# radio.net
KiCad netlist of a schematic drawn in EAGLE
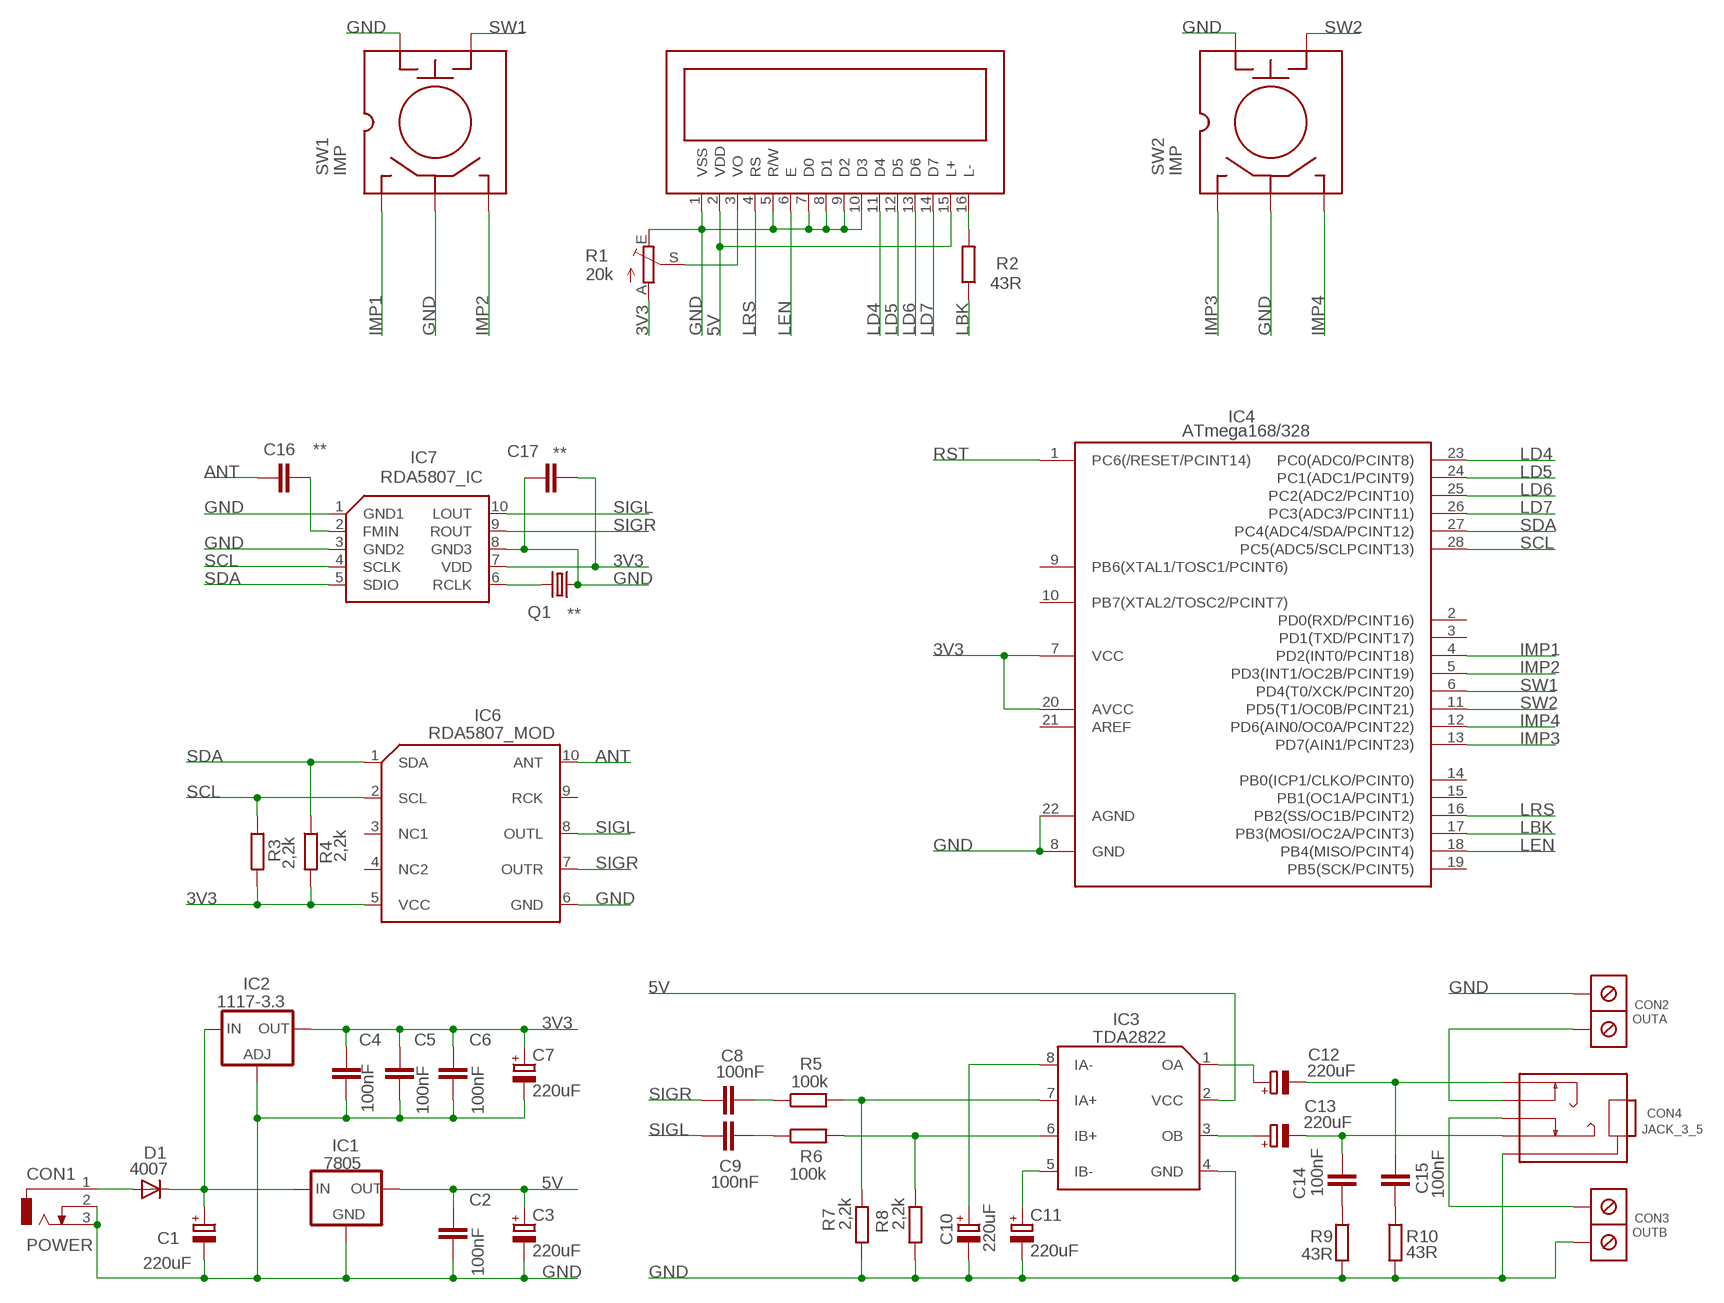
[diagram p0: schematic, sheet 1]

(export (version "E")
  (design (tool "Eeschema 10.0.6"))
  (components
    (comp (ref "C1")
      (value "220uF")
      (footprint "eagle-import:E2,5-7")
      (libsource (lib "eagle-import") (part "CPOL-EUE2.5-7"))
    )
    (comp (ref "C2")
      (value "100nF")
      (footprint "eagle-import:C050-030X075")
      (libsource (lib "eagle-import") (part "C-EU050-030X075"))
    )
    (comp (ref "C3")
      (value "220uF")
      (footprint "eagle-import:E2,5-7")
      (libsource (lib "eagle-import") (part "CPOL-EUE2.5-7"))
    )
    (comp (ref "C4")
      (value "100nF")
      (footprint "eagle-import:C050-030X075")
      (libsource (lib "eagle-import") (part "C-EU050-030X075"))
    )
    (comp (ref "C5")
      (value "100nF")
      (footprint "eagle-import:C050-030X075")
      (libsource (lib "eagle-import") (part "C-EU050-030X075"))
    )
    (comp (ref "C6")
      (value "100nF")
      (footprint "eagle-import:C050-030X075")
      (libsource (lib "eagle-import") (part "C-EU050-030X075"))
    )
    (comp (ref "C7")
      (value "220uF")
      (footprint "eagle-import:E2,5-7")
      (libsource (lib "eagle-import") (part "CPOL-EUE2.5-7"))
    )
    (comp (ref "C8")
      (value "100nF")
      (footprint "eagle-import:C050-030X075")
      (libsource (lib "eagle-import") (part "C-EU050-030X075"))
    )
    (comp (ref "C9")
      (value "100nF")
      (footprint "eagle-import:C050-030X075")
      (libsource (lib "eagle-import") (part "C-EU050-030X075"))
    )
    (comp (ref "C10")
      (value "220uF")
      (footprint "eagle-import:E2,5-7")
      (libsource (lib "eagle-import") (part "CPOL-EUE2.5-7"))
    )
    (comp (ref "C11")
      (value "220uF")
      (footprint "eagle-import:E2,5-7")
      (libsource (lib "eagle-import") (part "CPOL-EUE2.5-7"))
    )
    (comp (ref "C12")
      (value "220uF")
      (footprint "eagle-import:E2,5-7")
      (libsource (lib "eagle-import") (part "CPOL-EUE2.5-7"))
    )
    (comp (ref "C13")
      (value "220uF")
      (footprint "eagle-import:E2,5-7")
      (libsource (lib "eagle-import") (part "CPOL-EUE2.5-7"))
    )
    (comp (ref "C14")
      (value "100nF")
      (footprint "eagle-import:C050-030X075")
      (libsource (lib "eagle-import") (part "C-EU050-030X075"))
    )
    (comp (ref "C15")
      (value "100nF")
      (footprint "eagle-import:C050-030X075")
      (libsource (lib "eagle-import") (part "C-EU050-030X075"))
    )
    (comp (ref "C16")
      (value "**")
      (footprint "eagle-import:C0805K")
      (libsource (lib "eagle-import") (part "C-EUC0805K"))
    )
    (comp (ref "C17")
      (value "**")
      (footprint "eagle-import:C0805K")
      (libsource (lib "eagle-import") (part "C-EUC0805K"))
    )
    (comp (ref "CON1")
      (value "POWER")
      (footprint "eagle-import:DCJ0202")
      (libsource (lib "eagle-import") (part "DCJ0202"))
    )
    (comp (ref "CON2")
      (value "OUTA")
      (footprint "eagle-import:ARK2_300")
      (libsource (lib "eagle-import") (part "ARK2/300"))
    )
    (comp (ref "CON3")
      (value "OUTB")
      (footprint "eagle-import:ARK2_300")
      (libsource (lib "eagle-import") (part "ARK2/300"))
    )
    (comp (ref "CON4")
      (value "JACK_3_5")
      (footprint "eagle-import:JACK_3_5")
      (libsource (lib "eagle-import") (part "JACK_3_5"))
    )
    (comp (ref "D1")
      (value "4007")
      (footprint "eagle-import:DO41-10")
      (libsource (lib "eagle-import") (part "1N4004"))
    )
    (comp (ref "IC1")
      (value "7805")
      (footprint "eagle-import:78XXS")
      (libsource (lib "eagle-import") (part "78XXS"))
    )
    (comp (ref "IC2")
      (value "1117-3.3")
      (footprint "eagle-import:317TS")
      (libsource (lib "eagle-import") (part "LM317TS"))
    )
    (comp (ref "IC3")
      (value "TDA2822")
      (footprint "eagle-import:DIL8")
      (libsource (lib "eagle-import") (part "TDA2822"))
    )
    (comp (ref "IC4")
      (value "ATmega168/328")
      (footprint "eagle-import:DIL28-3")
      (libsource (lib "eagle-import") (part "MEGA48/88/168-PU"))
    )
    (comp (ref "IC5")
      (value "LCD16X2")
      (footprint "eagle-import:LCD16X2")
      (libsource (lib "eagle-import") (part "LCD16X2"))
    )
    (comp (ref "IC6")
      (value "RDA5807_MOD")
      (footprint "eagle-import:RDA5807_MOD")
      (libsource (lib "eagle-import") (part "RDA5807_MOD"))
    )
    (comp (ref "IC7")
      (value "RDA5807_IC")
      (footprint "eagle-import:MSOP10")
      (libsource (lib "eagle-import") (part "RDA5807_IC"))
    )
    (comp (ref "Q1")
      (value "**")
      (footprint "eagle-import:TC38H")
      (libsource (lib "eagle-import") (part "CRYSTALTC38H"))
    )
    (comp (ref "R1")
      (value "20k")
      (footprint "eagle-import:CA6V")
      (libsource (lib "eagle-import") (part "TRIM_EU-CA6V"))
    )
    (comp (ref "R2")
      (value "43R")
      (footprint "eagle-import:0207_7")
      (libsource (lib "eagle-import") (part "R-EU_0207/7"))
    )
    (comp (ref "R3")
      (value "2,2k")
      (footprint "eagle-import:0207_7")
      (libsource (lib "eagle-import") (part "R-EU_0207/7"))
    )
    (comp (ref "R4")
      (value "2,2k")
      (footprint "eagle-import:0207_7")
      (libsource (lib "eagle-import") (part "R-EU_0207/7"))
    )
    (comp (ref "R5")
      (value "100k")
      (footprint "eagle-import:0207_7")
      (libsource (lib "eagle-import") (part "R-EU_0207/7"))
    )
    (comp (ref "R6")
      (value "100k")
      (footprint "eagle-import:0207_7")
      (libsource (lib "eagle-import") (part "R-EU_0207/7"))
    )
    (comp (ref "R7")
      (value "2,2k")
      (footprint "eagle-import:0207_7")
      (libsource (lib "eagle-import") (part "R-EU_0207/7"))
    )
    (comp (ref "R8")
      (value "2,2k")
      (footprint "eagle-import:0207_7")
      (libsource (lib "eagle-import") (part "R-EU_0207/7"))
    )
    (comp (ref "R9")
      (value "43R")
      (footprint "eagle-import:0207_7")
      (libsource (lib "eagle-import") (part "R-EU_0207/7"))
    )
    (comp (ref "R10")
      (value "43R")
      (footprint "eagle-import:0207_7")
      (libsource (lib "eagle-import") (part "R-EU_0207/7"))
    )
    (comp (ref "SW1")
      (value "IMP")
      (footprint "eagle-import:IMP")
      (libsource (lib "eagle-import") (part "IMP"))
    )
    (comp (ref "SW2")
      (value "IMP")
      (footprint "eagle-import:IMP")
      (libsource (lib "eagle-import") (part "IMP"))
    )
  )
  (nets
    (net (code "1") (name "/3V3") (class "Default")
      (node (ref "C17") (pin "2") (pinfunction "2_2") (pintype "passive"))
      (node (ref "C4") (pin "1") (pinfunction "1_1") (pintype "passive"))
      (node (ref "C5") (pin "1") (pinfunction "1_1") (pintype "passive"))
      (node (ref "C6") (pin "1") (pinfunction "1_1") (pintype "passive"))
      (node (ref "C7") (pin "+") (pinfunction "+_+") (pintype "passive"))
      (node (ref "IC2") (pin "2") (pinfunction "OUT_2") (pintype "passive"))
      (node (ref "IC4") (pin "20") (pinfunction "AVCC_20") (pintype "passive"))
      (node (ref "IC4") (pin "7") (pinfunction "VCC_7") (pintype "power_in"))
      (node (ref "IC6") (pin "5") (pinfunction "VCC_5") (pintype "bidirectional"))
      (node (ref "IC7") (pin "7") (pinfunction "VDD_7") (pintype "bidirectional"))
      (node (ref "R1") (pin "A") (pinfunction "A_A") (pintype "passive"))
      (node (ref "R3") (pin "2") (pinfunction "2_2") (pintype "passive"))
      (node (ref "R4") (pin "2") (pinfunction "2_2") (pintype "passive"))
    )
    (net (code "2") (name "/5V") (class "Default")
      (node (ref "C2") (pin "1") (pinfunction "1_1") (pintype "passive"))
      (node (ref "C3") (pin "+") (pinfunction "+_+") (pintype "passive"))
      (node (ref "IC1") (pin "OUT") (pinfunction "OUT_OUT") (pintype "passive"))
      (node (ref "IC3") (pin "2") (pinfunction "VCC_2") (pintype "bidirectional"))
      (node (ref "IC5") (pin "15") (pinfunction "L+_15") (pintype "bidirectional"))
      (node (ref "IC5") (pin "2") (pinfunction "VDD_2") (pintype "bidirectional"))
    )
    (net (code "3") (name "/ANT") (class "Default")
      (node (ref "C16") (pin "1") (pinfunction "1_1") (pintype "passive"))
      (node (ref "IC6") (pin "10") (pinfunction "ANT_10") (pintype "bidirectional"))
    )
    (net (code "4") (name "/GND") (class "Default")
      (node (ref "C1") (pin "-") (pinfunction "-_-") (pintype "passive"))
      (node (ref "C10") (pin "-") (pinfunction "-_-") (pintype "passive"))
      (node (ref "C11") (pin "-") (pinfunction "-_-") (pintype "passive"))
      (node (ref "C17") (pin "1") (pinfunction "1_1") (pintype "passive"))
      (node (ref "C2") (pin "2") (pinfunction "2_2") (pintype "passive"))
      (node (ref "C3") (pin "-") (pinfunction "-_-") (pintype "passive"))
      (node (ref "C4") (pin "2") (pinfunction "2_2") (pintype "passive"))
      (node (ref "C5") (pin "2") (pinfunction "2_2") (pintype "passive"))
      (node (ref "C6") (pin "2") (pinfunction "2_2") (pintype "passive"))
      (node (ref "C7") (pin "-") (pinfunction "-_-") (pintype "passive"))
      (node (ref "CON1") (pin "2") (pinfunction "2_2") (pintype "passive"))
      (node (ref "CON1") (pin "3") (pinfunction "3_3") (pintype "passive"))
      (node (ref "CON2") (pin "2") (pinfunction "2_2") (pintype "bidirectional"))
      (node (ref "CON3") (pin "1") (pinfunction "1_1") (pintype "bidirectional"))
      (node (ref "CON4") (pin "G") (pinfunction "G_G") (pintype "bidirectional"))
      (node (ref "IC1") (pin "GND") (pinfunction "GND_GND") (pintype "input"))
      (node (ref "IC2") (pin "1") (pinfunction "ADJ_1") (pintype "input"))
      (node (ref "IC3") (pin "4") (pinfunction "GND_4") (pintype "bidirectional"))
      (node (ref "IC4") (pin "22") (pinfunction "AGND_22") (pintype "power_in"))
      (node (ref "IC4") (pin "8") (pinfunction "GND_8") (pintype "power_in"))
      (node (ref "IC5") (pin "1") (pinfunction "VSS_1") (pintype "bidirectional"))
      (node (ref "IC5") (pin "10") (pinfunction "D3_10") (pintype "bidirectional"))
      (node (ref "IC5") (pin "5") (pinfunction "R/W_5") (pintype "bidirectional"))
      (node (ref "IC5") (pin "7") (pinfunction "D0_7") (pintype "bidirectional"))
      (node (ref "IC5") (pin "8") (pinfunction "D1_8") (pintype "bidirectional"))
      (node (ref "IC5") (pin "9") (pinfunction "D2_9") (pintype "bidirectional"))
      (node (ref "IC6") (pin "6") (pinfunction "GND_6") (pintype "bidirectional"))
      (node (ref "IC7") (pin "1") (pinfunction "GND1_1") (pintype "bidirectional"))
      (node (ref "IC7") (pin "3") (pinfunction "GND2_3") (pintype "bidirectional"))
      (node (ref "IC7") (pin "8") (pinfunction "GND3_8") (pintype "bidirectional"))
      (node (ref "Q1") (pin "1") (pinfunction "1_1") (pintype "passive"))
      (node (ref "R1") (pin "E") (pinfunction "E_E") (pintype "passive"))
      (node (ref "R10") (pin "2") (pinfunction "2_2") (pintype "passive"))
      (node (ref "R7") (pin "2") (pinfunction "2_2") (pintype "passive"))
      (node (ref "R8") (pin "2") (pinfunction "2_2") (pintype "passive"))
      (node (ref "R9") (pin "2") (pinfunction "2_2") (pintype "passive"))
      (node (ref "SW1") (pin "2") (pinfunction "2_2") (pintype "bidirectional"))
      (node (ref "SW1") (pin "5") (pinfunction "5_5") (pintype "bidirectional"))
      (node (ref "SW2") (pin "2") (pinfunction "2_2") (pintype "bidirectional"))
      (node (ref "SW2") (pin "5") (pinfunction "5_5") (pintype "bidirectional"))
    )
    (net (code "5") (name "/IMP1") (class "Default")
      (node (ref "IC4") (pin "4") (pinfunction "PD2(INT0/PCINT18)_4") (pintype "bidirectional"))
      (node (ref "SW1") (pin "1") (pinfunction "1_1") (pintype "bidirectional"))
    )
    (net (code "6") (name "/IMP2") (class "Default")
      (node (ref "IC4") (pin "5") (pinfunction "PD3(INT1/OC2B/PCINT19)_5") (pintype "bidirectional"))
      (node (ref "SW1") (pin "3") (pinfunction "3_3") (pintype "bidirectional"))
    )
    (net (code "7") (name "/IMP3") (class "Default")
      (node (ref "IC4") (pin "13") (pinfunction "PD7(AIN1/PCINT23)_13") (pintype "bidirectional"))
      (node (ref "SW2") (pin "1") (pinfunction "1_1") (pintype "bidirectional"))
    )
    (net (code "8") (name "/IMP4") (class "Default")
      (node (ref "IC4") (pin "12") (pinfunction "PD6(AIN0/OC0A/PCINT22)_12") (pintype "bidirectional"))
      (node (ref "SW2") (pin "3") (pinfunction "3_3") (pintype "bidirectional"))
    )
    (net (code "9") (name "/LBK") (class "Default")
      (node (ref "IC4") (pin "17") (pinfunction "PB3(MOSI/OC2A/PCINT3)_17") (pintype "bidirectional"))
      (node (ref "R2") (pin "1") (pinfunction "1_1") (pintype "passive"))
    )
    (net (code "10") (name "/LD4") (class "Default")
      (node (ref "IC4") (pin "23") (pinfunction "PC0(ADC0/PCINT8)_23") (pintype "bidirectional"))
      (node (ref "IC5") (pin "11") (pinfunction "D4_11") (pintype "bidirectional"))
    )
    (net (code "11") (name "/LD5") (class "Default")
      (node (ref "IC4") (pin "24") (pinfunction "PC1(ADC1/PCINT9)_24") (pintype "bidirectional"))
      (node (ref "IC5") (pin "12") (pinfunction "D5_12") (pintype "bidirectional"))
    )
    (net (code "12") (name "/LD6") (class "Default")
      (node (ref "IC4") (pin "25") (pinfunction "PC2(ADC2/PCINT10)_25") (pintype "bidirectional"))
      (node (ref "IC5") (pin "13") (pinfunction "D6_13") (pintype "bidirectional"))
    )
    (net (code "13") (name "/LD7") (class "Default")
      (node (ref "IC4") (pin "26") (pinfunction "PC3(ADC3/PCINT11)_26") (pintype "bidirectional"))
      (node (ref "IC5") (pin "14") (pinfunction "D7_14") (pintype "bidirectional"))
    )
    (net (code "14") (name "/LEN") (class "Default")
      (node (ref "IC4") (pin "18") (pinfunction "PB4(MISO/PCINT4)_18") (pintype "bidirectional"))
      (node (ref "IC5") (pin "6") (pinfunction "E_6") (pintype "bidirectional"))
    )
    (net (code "15") (name "/LRS") (class "Default")
      (node (ref "IC4") (pin "16") (pinfunction "PB2(SS/OC1B/PCINT2)_16") (pintype "bidirectional"))
      (node (ref "IC5") (pin "4") (pinfunction "RS_4") (pintype "bidirectional"))
    )
    (net (code "16") (name "/RST") (class "Default")
      (node (ref "IC4") (pin "1") (pinfunction "PC6(/RESET/PCINT14)_1") (pintype "bidirectional"))
    )
    (net (code "17") (name "/SCL") (class "Default")
      (node (ref "IC4") (pin "28") (pinfunction "PC5(ADC5/SCLPCINT13)_28") (pintype "bidirectional"))
      (node (ref "IC6") (pin "2") (pinfunction "SCL_2") (pintype "bidirectional"))
      (node (ref "IC7") (pin "4") (pinfunction "SCLK_4") (pintype "bidirectional"))
      (node (ref "R3") (pin "1") (pinfunction "1_1") (pintype "passive"))
    )
    (net (code "18") (name "/SDA") (class "Default")
      (node (ref "IC4") (pin "27") (pinfunction "PC4(ADC4/SDA/PCINT12)_27") (pintype "bidirectional"))
      (node (ref "IC6") (pin "1") (pinfunction "SDA_1") (pintype "bidirectional"))
      (node (ref "IC7") (pin "5") (pinfunction "SDIO_5") (pintype "bidirectional"))
      (node (ref "R4") (pin "1") (pinfunction "1_1") (pintype "passive"))
    )
    (net (code "19") (name "/SIGL") (class "Default")
      (node (ref "C9") (pin "1") (pinfunction "1_1") (pintype "passive"))
      (node (ref "IC6") (pin "8") (pinfunction "OUTL_8") (pintype "bidirectional"))
      (node (ref "IC7") (pin "10") (pinfunction "LOUT_10") (pintype "bidirectional"))
    )
    (net (code "20") (name "/SIGR") (class "Default")
      (node (ref "C8") (pin "1") (pinfunction "1_1") (pintype "passive"))
      (node (ref "IC6") (pin "7") (pinfunction "OUTR_7") (pintype "bidirectional"))
      (node (ref "IC7") (pin "9") (pinfunction "ROUT_9") (pintype "bidirectional"))
    )
    (net (code "21") (name "/SW1") (class "Default")
      (node (ref "IC4") (pin "6") (pinfunction "PD4(T0/XCK/PCINT20)_6") (pintype "bidirectional"))
      (node (ref "SW1") (pin "4") (pinfunction "4_4") (pintype "bidirectional"))
    )
    (net (code "22") (name "/SW2") (class "Default")
      (node (ref "IC4") (pin "11") (pinfunction "PD5(T1/OC0B/PCINT21)_11") (pintype "bidirectional"))
      (node (ref "SW2") (pin "4") (pinfunction "4_4") (pintype "bidirectional"))
    )
    (net (code "23") (name "Net-(C8-Pad2)") (class "Default")
      (node (ref "C8") (pin "2") (pinfunction "2_2") (pintype "passive"))
      (node (ref "R5") (pin "1") (pinfunction "1_1") (pintype "passive"))
    )
    (net (code "24") (name "Net-(C9-Pad2)") (class "Default")
      (node (ref "C9") (pin "2") (pinfunction "2_2") (pintype "passive"))
      (node (ref "R6") (pin "1") (pinfunction "1_1") (pintype "passive"))
    )
    (net (code "25") (name "Net-(C12-Pad-)") (class "Default")
      (node (ref "C12") (pin "-") (pinfunction "-_-") (pintype "passive"))
      (node (ref "C15") (pin "2") (pinfunction "2_2") (pintype "passive"))
      (node (ref "CON4") (pin "R") (pinfunction "R_R") (pintype "bidirectional"))
    )
    (net (code "26") (name "Net-(C13-Pad-)") (class "Default")
      (node (ref "C13") (pin "-") (pinfunction "-_-") (pintype "passive"))
      (node (ref "C14") (pin "2") (pinfunction "2_2") (pintype "passive"))
      (node (ref "CON4") (pin "L") (pinfunction "L_L") (pintype "bidirectional"))
    )
    (net (code "27") (name "Net-(C14-Pad1)") (class "Default")
      (node (ref "C14") (pin "1") (pinfunction "1_1") (pintype "passive"))
      (node (ref "R9") (pin "1") (pinfunction "1_1") (pintype "passive"))
    )
    (net (code "28") (name "Net-(C15-Pad1)") (class "Default")
      (node (ref "C15") (pin "1") (pinfunction "1_1") (pintype "passive"))
      (node (ref "R10") (pin "1") (pinfunction "1_1") (pintype "passive"))
    )
    (net (code "29") (name "Net-(CON1-Pad1)") (class "Default")
      (node (ref "CON1") (pin "1") (pinfunction "1_1") (pintype "passive"))
      (node (ref "D1") (pin "A") (pinfunction "A_A") (pintype "passive"))
    )
    (net (code "30") (name "Net-(CON2-Pad1)") (class "Default")
      (node (ref "CON2") (pin "1") (pinfunction "1_1") (pintype "bidirectional"))
      (node (ref "CON4") (pin "RW") (pinfunction "RW_RW") (pintype "bidirectional"))
    )
    (net (code "31") (name "Net-(CON3-Pad2)") (class "Default")
      (node (ref "CON3") (pin "2") (pinfunction "2_2") (pintype "bidirectional"))
      (node (ref "CON4") (pin "LW") (pinfunction "LW_LW") (pintype "bidirectional"))
    )
    (net (code "32") (name "Net-(IC2-IN)") (class "Default")
      (node (ref "C1") (pin "+") (pinfunction "+_+") (pintype "passive"))
      (node (ref "D1") (pin "C") (pinfunction "C_C") (pintype "passive"))
      (node (ref "IC1") (pin "IN") (pinfunction "IN_IN") (pintype "input"))
      (node (ref "IC2") (pin "3") (pinfunction "IN_3") (pintype "input"))
    )
    (net (code "33") (name "Net-(IC3-IA+)") (class "Default")
      (node (ref "IC3") (pin "7") (pinfunction "IA+_7") (pintype "bidirectional"))
      (node (ref "R5") (pin "2") (pinfunction "2_2") (pintype "passive"))
      (node (ref "R7") (pin "1") (pinfunction "1_1") (pintype "passive"))
    )
    (net (code "34") (name "Net-(IC3-IA-)") (class "Default")
      (node (ref "C10") (pin "+") (pinfunction "+_+") (pintype "passive"))
      (node (ref "IC3") (pin "8") (pinfunction "IA-_8") (pintype "bidirectional"))
    )
    (net (code "35") (name "Net-(IC3-IB+)") (class "Default")
      (node (ref "IC3") (pin "6") (pinfunction "IB+_6") (pintype "bidirectional"))
      (node (ref "R6") (pin "2") (pinfunction "2_2") (pintype "passive"))
      (node (ref "R8") (pin "1") (pinfunction "1_1") (pintype "passive"))
    )
    (net (code "36") (name "Net-(IC3-IB-)") (class "Default")
      (node (ref "C11") (pin "+") (pinfunction "+_+") (pintype "passive"))
      (node (ref "IC3") (pin "5") (pinfunction "IB-_5") (pintype "bidirectional"))
    )
    (net (code "37") (name "Net-(IC3-OA)") (class "Default")
      (node (ref "C12") (pin "+") (pinfunction "+_+") (pintype "passive"))
      (node (ref "IC3") (pin "1") (pinfunction "OA_1") (pintype "bidirectional"))
    )
    (net (code "38") (name "Net-(IC3-OB)") (class "Default")
      (node (ref "C13") (pin "+") (pinfunction "+_+") (pintype "passive"))
      (node (ref "IC3") (pin "3") (pinfunction "OB_3") (pintype "bidirectional"))
    )
    (net (code "39") (name "Net-(IC5-L-)") (class "Default")
      (node (ref "IC5") (pin "16") (pinfunction "L-_16") (pintype "bidirectional"))
      (node (ref "R2") (pin "2") (pinfunction "2_2") (pintype "passive"))
    )
    (net (code "40") (name "Net-(IC5-VO)") (class "Default")
      (node (ref "IC5") (pin "3") (pinfunction "VO_3") (pintype "bidirectional"))
      (node (ref "R1") (pin "S") (pinfunction "S_S") (pintype "passive"))
    )
    (net (code "41") (name "Net-(IC7-FMIN)") (class "Default")
      (node (ref "C16") (pin "2") (pinfunction "2_2") (pintype "passive"))
      (node (ref "IC7") (pin "2") (pinfunction "FMIN_2") (pintype "bidirectional"))
    )
    (net (code "42") (name "Net-(IC7-RCLK)") (class "Default")
      (node (ref "IC7") (pin "6") (pinfunction "RCLK_6") (pintype "bidirectional"))
      (node (ref "Q1") (pin "2") (pinfunction "2_2") (pintype "passive"))
    )
    (net (code "43") (name "unconnected-(IC4-AREF-Pad21)") (class "Default")
      (node (ref "IC4") (pin "21") (pinfunction "AREF_21") (pintype "passive"))
    )
    (net (code "44") (name "unconnected-(IC4-PB0(ICP1{slash}CLKO{slash}PCINT0)-Pad14)") (class "Default")
      (node (ref "IC4") (pin "14") (pinfunction "PB0(ICP1/CLKO/PCINT0)_14") (pintype "bidirectional"))
    )
    (net (code "45") (name "unconnected-(IC4-PB1(OC1A{slash}PCINT1)-Pad15)") (class "Default")
      (node (ref "IC4") (pin "15") (pinfunction "PB1(OC1A/PCINT1)_15") (pintype "bidirectional"))
    )
    (net (code "46") (name "unconnected-(IC4-PB5(SCK{slash}PCINT5)-Pad19)") (class "Default")
      (node (ref "IC4") (pin "19") (pinfunction "PB5(SCK/PCINT5)_19") (pintype "bidirectional"))
    )
    (net (code "47") (name "unconnected-(IC4-PB6(XTAL1{slash}TOSC1{slash}PCINT6)-Pad9)") (class "Default")
      (node (ref "IC4") (pin "9") (pinfunction "PB6(XTAL1/TOSC1/PCINT6)_9") (pintype "bidirectional"))
    )
    (net (code "48") (name "unconnected-(IC4-PB7(XTAL2{slash}TOSC2{slash}PCINT7)-Pad10)") (class "Default")
      (node (ref "IC4") (pin "10") (pinfunction "PB7(XTAL2/TOSC2/PCINT7)_10") (pintype "bidirectional"))
    )
    (net (code "49") (name "unconnected-(IC4-PD0(RXD{slash}PCINT16)-Pad2)") (class "Default")
      (node (ref "IC4") (pin "2") (pinfunction "PD0(RXD/PCINT16)_2") (pintype "bidirectional"))
    )
    (net (code "50") (name "unconnected-(IC4-PD1(TXD{slash}PCINT17)-Pad3)") (class "Default")
      (node (ref "IC4") (pin "3") (pinfunction "PD1(TXD/PCINT17)_3") (pintype "bidirectional"))
    )
    (net (code "51") (name "unconnected-(IC6-NC1-Pad3)") (class "Default")
      (node (ref "IC6") (pin "3") (pinfunction "NC1_3") (pintype "bidirectional"))
    )
    (net (code "52") (name "unconnected-(IC6-NC2-Pad4)") (class "Default")
      (node (ref "IC6") (pin "4") (pinfunction "NC2_4") (pintype "bidirectional"))
    )
    (net (code "53") (name "unconnected-(IC6-RCK-Pad9)") (class "Default")
      (node (ref "IC6") (pin "9") (pinfunction "RCK_9") (pintype "bidirectional"))
    )
  )
)
